# 8266_DIYIOT_Board_L_AS_G_V.net
KiCad netlist of a schematic drawn in EAGLE
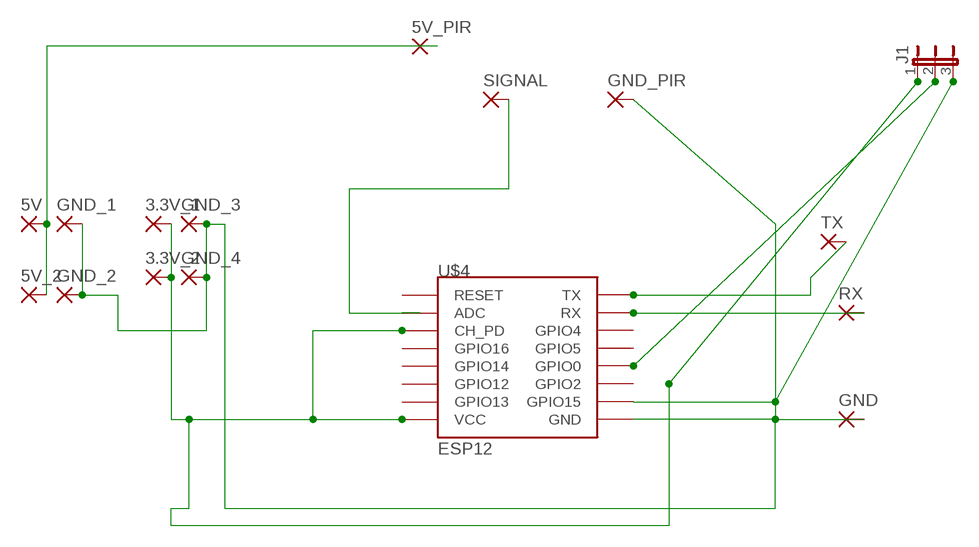
[diagram p0: schematic, sheet 1]

(export (version "E")
  (design (tool "Eeschema 10.0.6"))
  (components
    (comp (ref "3.3V_1")
      (value "2,15/1,0")
      (footprint "eagle-import:2,15_1,0")
      (libsource (lib "eagle-import") (part "2,15/1,0"))
    )
    (comp (ref "3.3V_2")
      (value "2,15/1,0")
      (footprint "eagle-import:2,15_1,0")
      (libsource (lib "eagle-import") (part "2,15/1,0"))
    )
    (comp (ref "5V")
      (value "2,15/1,0")
      (footprint "eagle-import:2,15_1,0")
      (libsource (lib "eagle-import") (part "2,15/1,0"))
    )
    (comp (ref "5V_2")
      (value "2,15/1,0")
      (footprint "eagle-import:2,15_1,0")
      (libsource (lib "eagle-import") (part "2,15/1,0"))
    )
    (comp (ref "5V_PIR")
      (value "2,15/1,0")
      (footprint "eagle-import:2,15_1,0")
      (libsource (lib "eagle-import") (part "2,15/1,0"))
    )
    (comp (ref "GND")
      (value "2,15/1,0")
      (footprint "eagle-import:2,15_1,0")
      (libsource (lib "eagle-import") (part "2,15/1,0"))
    )
    (comp (ref "GND_1")
      (value "2,15/1,0")
      (footprint "eagle-import:2,15_1,0")
      (libsource (lib "eagle-import") (part "2,15/1,0"))
    )
    (comp (ref "GND_2")
      (value "2,15/1,0")
      (footprint "eagle-import:2,15_1,0")
      (libsource (lib "eagle-import") (part "2,15/1,0"))
    )
    (comp (ref "GND_3")
      (value "2,15/1,0")
      (footprint "eagle-import:2,15_1,0")
      (libsource (lib "eagle-import") (part "2,15/1,0"))
    )
    (comp (ref "GND_4")
      (value "2,15/1,0")
      (footprint "eagle-import:2,15_1,0")
      (libsource (lib "eagle-import") (part "2,15/1,0"))
    )
    (comp (ref "GND_PIR")
      (value "2,15/1,0")
      (footprint "eagle-import:2,15_1,0")
      (libsource (lib "eagle-import") (part "2,15/1,0"))
    )
    (comp (ref "J1")
      (value "JP2E")
      (footprint "eagle-import:JP2")
      (libsource (lib "eagle-import") (part "JP2E"))
    )
    (comp (ref "RX")
      (value "2,15/1,0")
      (footprint "eagle-import:2,15_1,0")
      (libsource (lib "eagle-import") (part "2,15/1,0"))
    )
    (comp (ref "SIGNAL")
      (value "2,15/1,0")
      (footprint "eagle-import:2,15_1,0")
      (libsource (lib "eagle-import") (part "2,15/1,0"))
    )
    (comp (ref "TX")
      (value "2,15/1,0")
      (footprint "eagle-import:2,15_1,0")
      (libsource (lib "eagle-import") (part "2,15/1,0"))
    )
    (comp (ref "U$4")
      (value "ESP12")
      (footprint "eagle-import:ESP12")
      (libsource (lib "eagle-import") (part "ESP12"))
    )
  )
  (nets
    (net (code "1") (name "/5V") (class "Default")
      (node (ref "5V") (pin "1") (pinfunction "P_1") (pintype "passive"))
      (node (ref "5V_2") (pin "1") (pinfunction "P_1") (pintype "passive"))
      (node (ref "5V_PIR") (pin "1") (pinfunction "P_1") (pintype "passive"))
      (node (ref "GND") (pin "1") (pinfunction "P_1") (pintype "passive"))
      (node (ref "GND_1") (pin "1") (pinfunction "P_1") (pintype "passive"))
      (node (ref "GND_2") (pin "1") (pinfunction "P_1") (pintype "passive"))
      (node (ref "GND_3") (pin "1") (pinfunction "P_1") (pintype "passive"))
      (node (ref "GND_4") (pin "1") (pinfunction "P_1") (pintype "passive"))
      (node (ref "GND_PIR") (pin "1") (pinfunction "P_1") (pintype "passive"))
      (node (ref "J1") (pin "3") (pinfunction "3_3") (pintype "passive"))
      (node (ref "U$4") (pin "GND") (pinfunction "GND_GND") (pintype "bidirectional"))
      (node (ref "U$4") (pin "GPIO15") (pinfunction "GPIO15_GPIO15") (pintype "bidirectional"))
    )
    (net (code "2") (name "Net-(3.3V_1-P)") (class "Default")
      (node (ref "3.3V_1") (pin "1") (pinfunction "P_1") (pintype "passive"))
      (node (ref "3.3V_2") (pin "1") (pinfunction "P_1") (pintype "passive"))
      (node (ref "J1") (pin "1") (pinfunction "1_1") (pintype "passive"))
      (node (ref "U$4") (pin "CH_PD") (pinfunction "CH_PD_CH_PD") (pintype "bidirectional"))
      (node (ref "U$4") (pin "VCC") (pinfunction "VCC_VCC") (pintype "bidirectional"))
    )
    (net (code "3") (name "Net-(J1-Pad2)") (class "Default")
      (node (ref "J1") (pin "2") (pinfunction "2_2") (pintype "passive"))
      (node (ref "U$4") (pin "GPIO0") (pinfunction "GPIO0_GPIO0") (pintype "bidirectional"))
    )
    (net (code "4") (name "Net-(RX-P)") (class "Default")
      (node (ref "RX") (pin "1") (pinfunction "P_1") (pintype "passive"))
      (node (ref "U$4") (pin "RX") (pinfunction "RX_RX") (pintype "bidirectional"))
    )
    (net (code "5") (name "Net-(SIGNAL-P)") (class "Default")
      (node (ref "SIGNAL") (pin "1") (pinfunction "P_1") (pintype "passive"))
      (node (ref "U$4") (pin "ADC") (pinfunction "ADC_ADC") (pintype "bidirectional"))
    )
    (net (code "6") (name "Net-(TX-P)") (class "Default")
      (node (ref "TX") (pin "1") (pinfunction "P_1") (pintype "passive"))
      (node (ref "U$4") (pin "TX") (pinfunction "TX_TX") (pintype "bidirectional"))
    )
    (net (code "7") (name "unconnected-(U$4-PadGPIO2)") (class "Default")
      (node (ref "U$4") (pin "GPIO2") (pinfunction "GPIO2_GPIO2") (pintype "bidirectional"))
    )
    (net (code "8") (name "unconnected-(U$4-PadGPIO4)") (class "Default")
      (node (ref "U$4") (pin "GPIO4") (pinfunction "GPIO4_GPIO4") (pintype "bidirectional"))
    )
    (net (code "9") (name "unconnected-(U$4-PadGPIO5)") (class "Default")
      (node (ref "U$4") (pin "GPIO5") (pinfunction "GPIO5_GPIO5") (pintype "bidirectional"))
    )
    (net (code "10") (name "unconnected-(U$4-PadGPIO12)") (class "Default")
      (node (ref "U$4") (pin "GPIO12") (pinfunction "GPIO12_GPIO12") (pintype "bidirectional"))
    )
    (net (code "11") (name "unconnected-(U$4-PadGPIO13)") (class "Default")
      (node (ref "U$4") (pin "GPIO13") (pinfunction "GPIO13_GPIO13") (pintype "bidirectional"))
    )
    (net (code "12") (name "unconnected-(U$4-PadGPIO14)") (class "Default")
      (node (ref "U$4") (pin "GPIO14") (pinfunction "GPIO14_GPIO14") (pintype "bidirectional"))
    )
    (net (code "13") (name "unconnected-(U$4-PadGPIO16)") (class "Default")
      (node (ref "U$4") (pin "GPIO16") (pinfunction "GPIO16_GPIO16") (pintype "bidirectional"))
    )
    (net (code "14") (name "unconnected-(U$4-PadRESET)") (class "Default")
      (node (ref "U$4") (pin "RESET") (pinfunction "RESET_RESET") (pintype "bidirectional"))
    )
  )
)
